# IV_Converter.net
KiCad netlist of a schematic drawn in Altium Designer
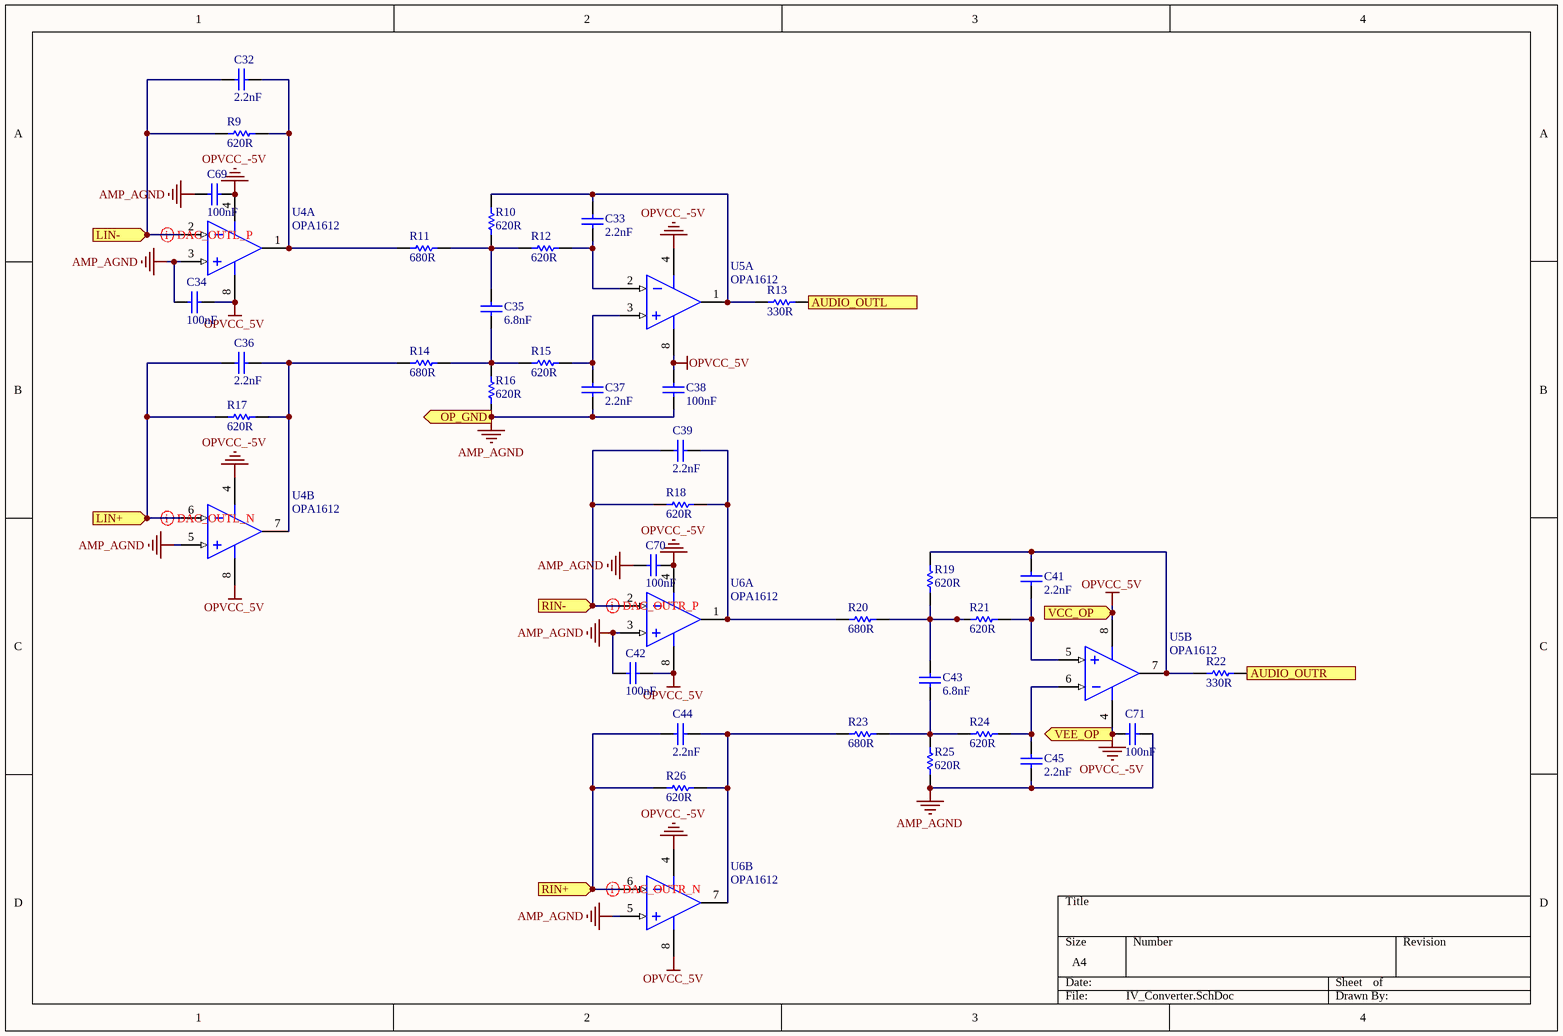
[diagram p0: IV_Converter.SchDoc]

(export (version "E")
  (design (tool "Eeschema 10.0.6"))
  (components
    (comp (ref "C32") (value "2.2nF") (footprint "SMC_0805") (libsource (lib "Common") (part "Cap Ceramic")))
    (comp (ref "C33") (value "2.2nF") (footprint "SMC_0805") (libsource (lib "Common") (part "Cap Ceramic")))
    (comp (ref "C34") (value "100nF") (footprint "SMC_0402") (libsource (lib "Common") (part "Cap Ceramic")))
    (comp (ref "C35") (value "6.8nF") (footprint "SMC_0805") (libsource (lib "Common") (part "Cap Ceramic")))
    (comp (ref "C36") (value "2.2nF") (footprint "SMC_0805") (libsource (lib "Common") (part "Cap Ceramic")))
    (comp (ref "C37") (value "2.2nF") (footprint "SMC_0805") (libsource (lib "Common") (part "Cap Ceramic")))
    (comp (ref "C38") (value "100nF") (footprint "SMC_0402") (libsource (lib "Common") (part "Cap Ceramic")))
    (comp (ref "C39") (value "2.2nF") (footprint "SMC_0805") (libsource (lib "Common") (part "Cap Ceramic")))
    (comp (ref "C41") (value "2.2nF") (footprint "SMC_0805") (libsource (lib "Common") (part "Cap Ceramic")))
    (comp (ref "C42") (value "100nF") (footprint "SMC_0402") (libsource (lib "Common") (part "Cap Ceramic")))
    (comp (ref "C43") (value "6.8nF") (footprint "SMC_0805") (libsource (lib "Common") (part "Cap Ceramic")))
    (comp (ref "C44") (value "2.2nF") (footprint "SMC_0805") (libsource (lib "Common") (part "Cap Ceramic")))
    (comp (ref "C45") (value "2.2nF") (footprint "SMC_0805") (libsource (lib "Common") (part "Cap Ceramic")))
    (comp (ref "C69") (value "100nF") (footprint "SMC_0402") (libsource (lib "Common") (part "Cap Ceramic")))
    (comp (ref "C70") (value "100nF") (footprint "SMC_0402") (libsource (lib "Common") (part "Cap Ceramic")))
    (comp (ref "C71") (value "100nF") (footprint "SMC_0402") (libsource (lib "Common") (part "Cap Ceramic")))
    (comp (ref "R9") (value "620R") (footprint "SMR_0805") (libsource (lib "Common") (part "Res SMT")))
    (comp (ref "R10") (value "620R") (footprint "SMR_0805") (libsource (lib "Common") (part "Res SMT")))
    (comp (ref "R11") (value "680R") (footprint "SMR_0805") (libsource (lib "Common") (part "Res SMT")))
    (comp (ref "R12") (value "620R") (footprint "SMR_0805") (libsource (lib "Common") (part "Res SMT")))
    (comp (ref "R13") (value "330R") (footprint "SMR_0805") (libsource (lib "Common") (part "Res SMT")))
    (comp (ref "R14") (value "680R") (footprint "SMR_0805") (libsource (lib "Common") (part "Res SMT")))
    (comp (ref "R15") (value "620R") (footprint "SMR_0805") (libsource (lib "Common") (part "Res SMT")))
    (comp (ref "R16") (value "620R") (footprint "SMR_0805") (libsource (lib "Common") (part "Res SMT")))
    (comp (ref "R17") (value "620R") (footprint "SMR_0805") (libsource (lib "Common") (part "Res SMT")))
    (comp (ref "R18") (value "620R") (footprint "SMR_0805") (libsource (lib "Common") (part "Res SMT")))
    (comp (ref "R19") (value "620R") (footprint "SMR_0805") (libsource (lib "Common") (part "Res SMT")))
    (comp (ref "R20") (value "680R") (footprint "SMR_0805") (libsource (lib "Common") (part "Res SMT")))
    (comp (ref "R21") (value "620R") (footprint "SMR_0805") (libsource (lib "Common") (part "Res SMT")))
    (comp (ref "R22") (value "330R") (footprint "SMR_0805") (libsource (lib "Common") (part "Res SMT")))
    (comp (ref "R23") (value "680R") (footprint "SMR_0805") (libsource (lib "Common") (part "Res SMT")))
    (comp (ref "R24") (value "620R") (footprint "SMR_0805") (libsource (lib "Common") (part "Res SMT")))
    (comp (ref "R25") (value "620R") (footprint "SMR_0805") (libsource (lib "Common") (part "Res SMT")))
    (comp (ref "R26") (value "620R") (footprint "SMR_0805") (libsource (lib "Common") (part "Res SMT")))
    (comp (ref "U4")
      (value "OPA1612")
      (footprint "SOIC127P600X175-8N")
      (libsource (lib "OpAmp") (part "LM358D"))
    )
    (comp (ref "U5")
      (value "OPA1612")
      (footprint "SOIC127P600X175-8N")
      (libsource (lib "OpAmp") (part "LM358D"))
    )
    (comp (ref "U6")
      (value "OPA1612")
      (footprint "SOIC127P600X175-8N")
      (libsource (lib "OpAmp") (part "LM358D"))
    )
  )
  (nets
    (net (code "1") (name "/AUDIO_OUTL") (class "Default")
      (node (ref "R13") (pin "2") (pinfunction "2_2") (pintype "passive"))
    )
    (net (code "2") (name "/AUDIO_OUTR") (class "Default")
      (node (ref "R22") (pin "2") (pinfunction "2_2") (pintype "passive"))
    )
    (net (code "3") (name "/LIN+") (class "Default")
      (node (ref "C36") (pin "1") (pinfunction "1_1") (pintype "passive"))
      (node (ref "R17") (pin "1") (pinfunction "1_1") (pintype "passive"))
      (node (ref "U4") (pin "6") (pinfunction "IN-_6") (pintype "input"))
    )
    (net (code "4") (name "/LIN-") (class "Default")
      (node (ref "C32") (pin "1") (pinfunction "1_1") (pintype "passive"))
      (node (ref "R9") (pin "1") (pinfunction "1_1") (pintype "passive"))
      (node (ref "U4") (pin "2") (pinfunction "IN-_2") (pintype "input"))
    )
    (net (code "5") (name "/RIN+") (class "Default")
      (node (ref "C44") (pin "1") (pinfunction "1_1") (pintype "passive"))
      (node (ref "R26") (pin "1") (pinfunction "1_1") (pintype "passive"))
      (node (ref "U6") (pin "6") (pinfunction "IN-_6") (pintype "input"))
    )
    (net (code "6") (name "/RIN-") (class "Default")
      (node (ref "C39") (pin "1") (pinfunction "1_1") (pintype "passive"))
      (node (ref "R18") (pin "1") (pinfunction "1_1") (pintype "passive"))
      (node (ref "U6") (pin "2") (pinfunction "IN-_2") (pintype "input"))
    )
    (net (code "7") (name "AMP_AGND") (class "Default")
      (node (ref "C34") (pin "1") (pinfunction "1_1") (pintype "passive"))
      (node (ref "C37") (pin "1") (pinfunction "1_1") (pintype "passive"))
      (node (ref "C38") (pin "1") (pinfunction "1_1") (pintype "passive"))
      (node (ref "C42") (pin "1") (pinfunction "1_1") (pintype "passive"))
      (node (ref "C45") (pin "1") (pinfunction "1_1") (pintype "passive"))
      (node (ref "C69") (pin "1") (pinfunction "1_1") (pintype "passive"))
      (node (ref "C70") (pin "1") (pinfunction "1_1") (pintype "passive"))
      (node (ref "C71") (pin "2") (pinfunction "2_2") (pintype "passive"))
      (node (ref "R16") (pin "1") (pinfunction "1_1") (pintype "passive"))
      (node (ref "R25") (pin "1") (pinfunction "1_1") (pintype "passive"))
      (node (ref "U4") (pin "3") (pinfunction "IN+_3") (pintype "input"))
      (node (ref "U4") (pin "5") (pinfunction "IN+_5") (pintype "input"))
      (node (ref "U6") (pin "3") (pinfunction "IN+_3") (pintype "input"))
      (node (ref "U6") (pin "5") (pinfunction "IN+_5") (pintype "input"))
    )
    (net (code "8") (name "Net-(C35-Pad1)") (class "Default")
      (node (ref "C35") (pin "1") (pinfunction "1_1") (pintype "passive"))
      (node (ref "R14") (pin "2") (pinfunction "2_2") (pintype "passive"))
      (node (ref "R15") (pin "2") (pinfunction "2_2") (pintype "passive"))
      (node (ref "R16") (pin "2") (pinfunction "2_2") (pintype "passive"))
    )
    (net (code "9") (name "Net-(C35-Pad2)") (class "Default")
      (node (ref "C35") (pin "2") (pinfunction "2_2") (pintype "passive"))
      (node (ref "R10") (pin "1") (pinfunction "1_1") (pintype "passive"))
      (node (ref "R11") (pin "2") (pinfunction "2_2") (pintype "passive"))
      (node (ref "R12") (pin "2") (pinfunction "2_2") (pintype "passive"))
    )
    (net (code "10") (name "Net-(C43-Pad1)") (class "Default")
      (node (ref "C43") (pin "1") (pinfunction "1_1") (pintype "passive"))
      (node (ref "R23") (pin "2") (pinfunction "2_2") (pintype "passive"))
      (node (ref "R24") (pin "2") (pinfunction "2_2") (pintype "passive"))
      (node (ref "R25") (pin "2") (pinfunction "2_2") (pintype "passive"))
    )
    (net (code "11") (name "Net-(C43-Pad2)") (class "Default")
      (node (ref "C43") (pin "2") (pinfunction "2_2") (pintype "passive"))
      (node (ref "R19") (pin "1") (pinfunction "1_1") (pintype "passive"))
      (node (ref "R20") (pin "2") (pinfunction "2_2") (pintype "passive"))
      (node (ref "R21") (pin "2") (pinfunction "2_2") (pintype "passive"))
    )
    (net (code "12") (name "Net-(U4A-OUT)") (class "Default")
      (node (ref "C32") (pin "2") (pinfunction "2_2") (pintype "passive"))
      (node (ref "R11") (pin "1") (pinfunction "1_1") (pintype "passive"))
      (node (ref "R9") (pin "2") (pinfunction "2_2") (pintype "passive"))
      (node (ref "U4") (pin "1") (pinfunction "OUT_1") (pintype "open_collector"))
    )
    (net (code "13") (name "Net-(U4B-OUT)") (class "Default")
      (node (ref "C36") (pin "2") (pinfunction "2_2") (pintype "passive"))
      (node (ref "R14") (pin "1") (pinfunction "1_1") (pintype "passive"))
      (node (ref "R17") (pin "2") (pinfunction "2_2") (pintype "passive"))
      (node (ref "U4") (pin "7") (pinfunction "OUT_7") (pintype "open_collector"))
    )
    (net (code "14") (name "Net-(U5A-IN+)") (class "Default")
      (node (ref "C37") (pin "2") (pinfunction "2_2") (pintype "passive"))
      (node (ref "R15") (pin "1") (pinfunction "1_1") (pintype "passive"))
      (node (ref "U5") (pin "3") (pinfunction "IN+_3") (pintype "input"))
    )
    (net (code "15") (name "Net-(U5A-IN-)") (class "Default")
      (node (ref "C33") (pin "1") (pinfunction "1_1") (pintype "passive"))
      (node (ref "R12") (pin "1") (pinfunction "1_1") (pintype "passive"))
      (node (ref "U5") (pin "2") (pinfunction "IN-_2") (pintype "input"))
    )
    (net (code "16") (name "Net-(U5A-OUT)") (class "Default")
      (node (ref "C33") (pin "2") (pinfunction "2_2") (pintype "passive"))
      (node (ref "R10") (pin "2") (pinfunction "2_2") (pintype "passive"))
      (node (ref "R13") (pin "1") (pinfunction "1_1") (pintype "passive"))
      (node (ref "U5") (pin "1") (pinfunction "OUT_1") (pintype "open_collector"))
    )
    (net (code "17") (name "Net-(U5B-IN+)") (class "Default")
      (node (ref "C41") (pin "1") (pinfunction "1_1") (pintype "passive"))
      (node (ref "R21") (pin "1") (pinfunction "1_1") (pintype "passive"))
      (node (ref "U5") (pin "5") (pinfunction "IN+_5") (pintype "input"))
    )
    (net (code "18") (name "Net-(U5B-IN-)") (class "Default")
      (node (ref "C45") (pin "2") (pinfunction "2_2") (pintype "passive"))
      (node (ref "R24") (pin "1") (pinfunction "1_1") (pintype "passive"))
      (node (ref "U5") (pin "6") (pinfunction "IN-_6") (pintype "input"))
    )
    (net (code "19") (name "Net-(U5B-OUT)") (class "Default")
      (node (ref "C41") (pin "2") (pinfunction "2_2") (pintype "passive"))
      (node (ref "R19") (pin "2") (pinfunction "2_2") (pintype "passive"))
      (node (ref "R22") (pin "1") (pinfunction "1_1") (pintype "passive"))
      (node (ref "U5") (pin "7") (pinfunction "OUT_7") (pintype "open_collector"))
    )
    (net (code "20") (name "Net-(U6A-OUT)") (class "Default")
      (node (ref "C39") (pin "2") (pinfunction "2_2") (pintype "passive"))
      (node (ref "R18") (pin "2") (pinfunction "2_2") (pintype "passive"))
      (node (ref "R20") (pin "1") (pinfunction "1_1") (pintype "passive"))
      (node (ref "U6") (pin "1") (pinfunction "OUT_1") (pintype "open_collector"))
    )
    (net (code "21") (name "Net-(U6B-OUT)") (class "Default")
      (node (ref "C44") (pin "2") (pinfunction "2_2") (pintype "passive"))
      (node (ref "R23") (pin "1") (pinfunction "1_1") (pintype "passive"))
      (node (ref "R26") (pin "2") (pinfunction "2_2") (pintype "passive"))
      (node (ref "U6") (pin "7") (pinfunction "OUT_7") (pintype "open_collector"))
    )
    (net (code "22") (name "OPVCC_-5V") (class "Default")
      (node (ref "C69") (pin "2") (pinfunction "2_2") (pintype "passive"))
      (node (ref "C70") (pin "2") (pinfunction "2_2") (pintype "passive"))
      (node (ref "C71") (pin "1") (pinfunction "1_1") (pintype "passive"))
      (node (ref "U4") (pin "4") (pinfunction "V-_4") (pintype "power_in"))
      (node (ref "U5") (pin "4") (pinfunction "V-_4") (pintype "power_in"))
      (node (ref "U6") (pin "4") (pinfunction "V-_4") (pintype "power_in"))
    )
    (net (code "23") (name "OPVCC_5V") (class "Default")
      (node (ref "C34") (pin "2") (pinfunction "2_2") (pintype "passive"))
      (node (ref "C38") (pin "2") (pinfunction "2_2") (pintype "passive"))
      (node (ref "C42") (pin "2") (pinfunction "2_2") (pintype "passive"))
      (node (ref "U4") (pin "8") (pinfunction "V+_8") (pintype "power_in"))
      (node (ref "U5") (pin "8") (pinfunction "V+_8") (pintype "power_in"))
      (node (ref "U6") (pin "8") (pinfunction "V+_8") (pintype "power_in"))
    )
  )
)
